# uController.net
KiCad netlist of a schematic drawn in Altium Designer
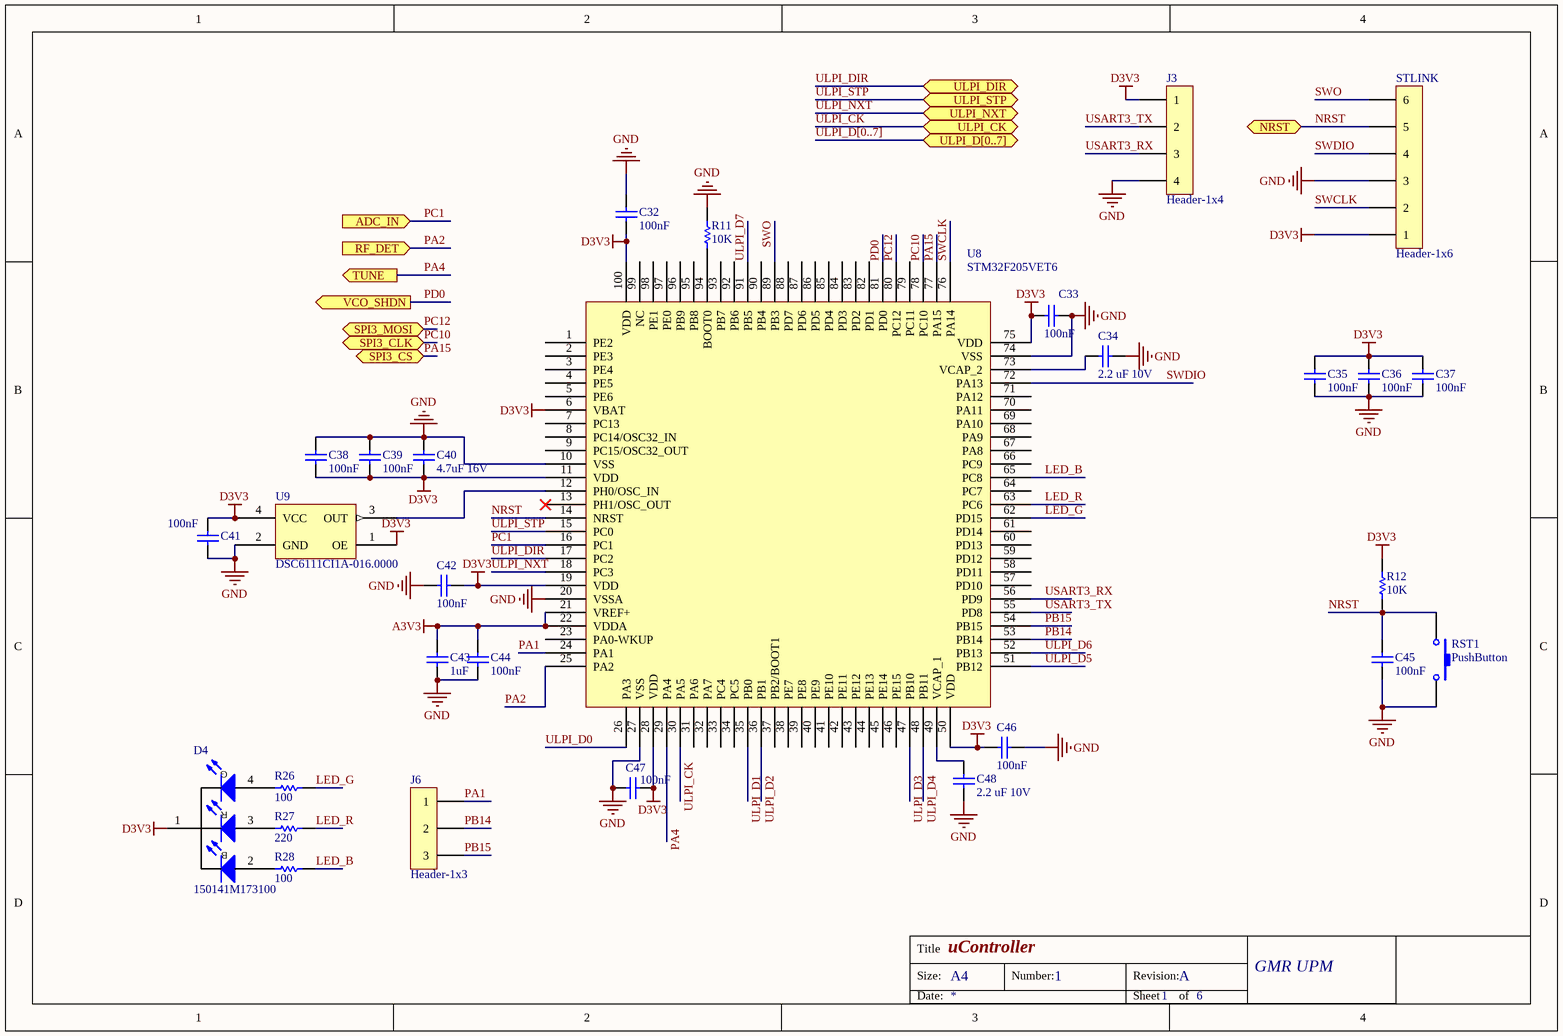
[diagram p0: uController.SchDoc]

(export (version "E")
  (design (tool "Eeschema 10.0.6"))
  (components
    (comp (ref "C32")
      (value "100nF")
      (footprint "0603 Cap")
      (description "CAP CER 0.1UF 16V X7R 0603")
      (fields
        (field (name "MANUFACTURER") "KEMET")
        (field (name "MANUFACTURER PART NUMBER") "C0603C104K4RACTU")
      )
      (libsource (lib "Componentes_base") (part "C0603C104K4RACTU"))
    )
    (comp (ref "C33")
      (value "100nF")
      (footprint "0603 Cap")
      (description "CAP CER 0.1UF 16V X7R 0603")
      (fields
        (field (name "MANUFACTURER") "KEMET")
        (field (name "MANUFACTURER PART NUMBER") "C0603C104K4RACTU")
      )
      (libsource (lib "Componentes_base") (part "C0603C104K4RACTU"))
    )
    (comp (ref "C34")
      (value "2.2 uF 10V")
      (footprint "0603 Cap")
      (description "CAP CER 2.2UF 10V X7R 0603")
      (fields
        (field (name "MANUFACTURER") "Samsung Electro-Mechanics America, Inc.")
        (field (name "MANUFACTURER PART NUMBER") "CL10B225KP8NNNC")
      )
      (libsource (lib "Componentes_base") (part "CL10B225KP8NNNC"))
    )
    (comp (ref "C35")
      (value "100nF")
      (footprint "0603 Cap")
      (description "CAP CER 0.1UF 16V X7R 0603")
      (fields
        (field (name "MANUFACTURER") "KEMET")
        (field (name "MANUFACTURER PART NUMBER") "C0603C104K4RACTU")
      )
      (libsource (lib "Componentes_base") (part "C0603C104K4RACTU"))
    )
    (comp (ref "C36")
      (value "100nF")
      (footprint "0603 Cap")
      (description "CAP CER 0.1UF 16V X7R 0603")
      (fields
        (field (name "MANUFACTURER") "KEMET")
        (field (name "MANUFACTURER PART NUMBER") "C0603C104K4RACTU")
      )
      (libsource (lib "Componentes_base") (part "C0603C104K4RACTU"))
    )
    (comp (ref "C37")
      (value "100nF")
      (footprint "0603 Cap")
      (description "CAP CER 0.1UF 16V X7R 0603")
      (fields
        (field (name "MANUFACTURER") "KEMET")
        (field (name "MANUFACTURER PART NUMBER") "C0603C104K4RACTU")
      )
      (libsource (lib "Componentes_base") (part "C0603C104K4RACTU"))
    )
    (comp (ref "C38")
      (value "100nF")
      (footprint "0603 Cap")
      (description "CAP CER 0.1UF 16V X7R 0603")
      (fields
        (field (name "MANUFACTURER") "KEMET")
        (field (name "MANUFACTURER PART NUMBER") "C0603C104K4RACTU")
      )
      (libsource (lib "Componentes_base") (part "C0603C104K4RACTU"))
    )
    (comp (ref "C39")
      (value "100nF")
      (footprint "0603 Cap")
      (description "CAP CER 0.1UF 16V X7R 0603")
      (fields
        (field (name "MANUFACTURER") "KEMET")
        (field (name "MANUFACTURER PART NUMBER") "C0603C104K4RACTU")
      )
      (libsource (lib "Componentes_base") (part "C0603C104K4RACTU"))
    )
    (comp (ref "C40")
      (value "4.7uF 16V")
      (footprint "0805 CAP")
      (description "CAP CER 4.7UF 16V X7R 0805")
      (fields
        (field (name "MANUFACTURER") "Murata Electronics North America")
        (field (name "MANUFACTURER PART NUMBER") "GRM21BR71C475KE51L")
      )
      (libsource (lib "Componentes_base") (part "GRM21BR71C475KE51L"))
    )
    (comp (ref "C41")
      (value "100nF")
      (footprint "0603 Cap")
      (description "CAP CER 0.1UF 16V X7R 0603")
      (fields
        (field (name "MANUFACTURER") "KEMET")
        (field (name "MANUFACTURER PART NUMBER") "C0603C104K4RACTU")
      )
      (libsource (lib "Componentes_base") (part "C0603C104K4RACTU"))
    )
    (comp (ref "C42")
      (value "100nF")
      (footprint "0603 Cap")
      (description "CAP CER 0.1UF 16V X7R 0603")
      (fields
        (field (name "MANUFACTURER") "KEMET")
        (field (name "MANUFACTURER PART NUMBER") "C0603C104K4RACTU")
      )
      (libsource (lib "Componentes_base") (part "C0603C104K4RACTU"))
    )
    (comp (ref "C43")
      (value "1uF")
      (footprint "0603 Cap")
      (description "CAP CER 1UF 16V X7R 0603")
      (fields
        (field (name "MANUFACTURER") "Samsung Electro-Mechanics America, Inc.")
        (field (name "MANUFACTURER PART NUMBER") "CL10B105MO8NNWC")
      )
      (libsource (lib "Componentes_base") (part "CL10B105MO8NNWC"))
    )
    (comp (ref "C44")
      (value "100nF")
      (footprint "0603 Cap")
      (description "CAP CER 0.1UF 16V X7R 0603")
      (fields
        (field (name "MANUFACTURER") "KEMET")
        (field (name "MANUFACTURER PART NUMBER") "C0603C104K4RACTU")
      )
      (libsource (lib "Componentes_base") (part "C0603C104K4RACTU"))
    )
    (comp (ref "C45")
      (value "100nF")
      (footprint "0603 Cap")
      (description "CAP CER 0.1UF 16V X7R 0603")
      (fields
        (field (name "MANUFACTURER") "KEMET")
        (field (name "MANUFACTURER PART NUMBER") "C0603C104K4RACTU")
      )
      (libsource (lib "Componentes_base") (part "C0603C104K4RACTU"))
    )
    (comp (ref "C46")
      (value "100nF")
      (footprint "0603 Cap")
      (description "CAP CER 0.1UF 16V X7R 0603")
      (fields
        (field (name "MANUFACTURER") "KEMET")
        (field (name "MANUFACTURER PART NUMBER") "C0603C104K4RACTU")
      )
      (libsource (lib "Componentes_base") (part "C0603C104K4RACTU"))
    )
    (comp (ref "C47")
      (value "100nF")
      (footprint "0603 Cap")
      (description "CAP CER 0.1UF 16V X7R 0603")
      (fields
        (field (name "MANUFACTURER") "KEMET")
        (field (name "MANUFACTURER PART NUMBER") "C0603C104K4RACTU")
      )
      (libsource (lib "Componentes_base") (part "C0603C104K4RACTU"))
    )
    (comp (ref "C48")
      (value "2.2 uF 10V")
      (footprint "0603 Cap")
      (description "CAP CER 2.2UF 10V X7R 0603")
      (fields
        (field (name "MANUFACTURER") "Samsung Electro-Mechanics America, Inc.")
        (field (name "MANUFACTURER PART NUMBER") "CL10B225KP8NNNC")
      )
      (libsource (lib "Componentes_base") (part "CL10B225KP8NNNC"))
    )
    (comp (ref "D4")
      (value "150141M173100")
      (footprint "DFN270P320X210-4N")
      (description "LED RGB CLEAR 1411 SMD")
      (fields (field (name "MANUFACTURER") "Wurth Electronics Inc."))
      (libsource (lib "Componentes_base") (part "150141M173100"))
    )
    (comp (ref "J3")
      (value "Header-1x4")
      (footprint "HEADER-1X4")
      (libsource (lib "B105connectors") (part "Header-1x4"))
    )
    (comp (ref "J6")
      (value "Header-1x3")
      (footprint "Header-1x3-Jumper")
      (libsource (lib "B105lib") (part "Header-1x3"))
    )
    (comp (ref "R11")
      (value "10K")
      (footprint "0603 Res")
      (description "RES SMD 10K OHM 1% 1/10W 0603")
      (fields
        (field (name "MANUFACTURER") "Yageo")
        (field (name "MANUFACTURER PART NUMBER") "RC0603FR-0710KL")
      )
      (libsource (lib "Componentes_base") (part "RC0603FR-0710KL"))
    )
    (comp (ref "R12")
      (value "10K")
      (footprint "0603 Res")
      (description "RES SMD 10K OHM 1% 1/10W 0603")
      (fields
        (field (name "MANUFACTURER") "Yageo")
        (field (name "MANUFACTURER PART NUMBER") "RC0603FR-0710KL")
      )
      (libsource (lib "Componentes_base") (part "RC0603FR-0710KL"))
    )
    (comp (ref "R26")
      (value "100")
      (footprint "RESC1005X04L")
      (description "RES 100 OHM 1/16W 1% 0402 SMD")
      (fields
        (field (name "MANUFACTURER") "Rohm Semiconductor")
        (field (name "MANUFACTURER PART NUMBER") "MCR01MRTF1000")
      )
      (libsource (lib "Componentes_base") (part "MCR01MRTF1000"))
    )
    (comp (ref "R27")
      (value "220")
      (footprint "RESC1005X04L")
      (description "RES SMD 220 OHM 1% 1/16W 0402")
      (fields
        (field (name "MANUFACTURER") "Yageo")
        (field (name "MANUFACTURER PART NUMBER") "RC0402FR-07220RL")
      )
      (libsource (lib "Componentes_base") (part "RC0402FR-07220RL"))
    )
    (comp (ref "R28")
      (value "100")
      (footprint "RESC1005X04L")
      (description "RES 100 OHM 1/16W 1% 0402 SMD")
      (fields
        (field (name "MANUFACTURER") "Rohm Semiconductor")
        (field (name "MANUFACTURER PART NUMBER") "MCR01MRTF1000")
      )
      (libsource (lib "Componentes_base") (part "MCR01MRTF1000"))
    )
    (comp (ref "RST1")
      (value "PushButton")
      (footprint "PushButton")
      (libsource (lib "B105lib") (part "PushButton"))
    )
    (comp (ref "STLINK")
      (value "Header-1x6")
      (footprint "Header-1x6")
      (libsource (lib "B105connectors") (part "Header-1x6"))
    )
    (comp (ref "U8")
      (value "STM32F205VET6")
      (footprint "LQFP-100")
      (description "IC MCU 32BIT 512KB FLASH 100LQFP")
      (fields (field (name "MANUFACTURER") "STMicroelectronics"))
      (libsource (lib "Componentes_base") (part "STM32F205VET6"))
    )
    (comp (ref "U9")
      (value "DSC6111CI1A-016.0000")
      (footprint "DFN 3.2x2.5")
      (description "ULTRA-LOW POWER,MEMS OSCILLATOR,")
      (fields (field (name "MANUFACTURER") "Microchip Technology"))
      (libsource (lib "Componentes_base") (part "DSC6111CI1A-016.0000"))
    )
  )
  (nets
    (net (code "1") (name "/LED_B") (class "Default")
      (node (ref "R28") (pin "2") (pinfunction "2_2") (pintype "passive"))
      (node (ref "U8") (pin "65") (pinfunction "PC8_65") (pintype "passive"))
    )
    (net (code "2") (name "/LED_G") (class "Default")
      (node (ref "R26") (pin "2") (pinfunction "2_2") (pintype "passive"))
      (node (ref "U8") (pin "62") (pinfunction "PD15_62") (pintype "passive"))
    )
    (net (code "3") (name "/LED_R") (class "Default")
      (node (ref "R27") (pin "2") (pinfunction "2_2") (pintype "passive"))
      (node (ref "U8") (pin "63") (pinfunction "PC6_63") (pintype "passive"))
    )
    (net (code "4") (name "/NRST") (class "Default")
      (node (ref "C45") (pin "2") (pinfunction "2_2") (pintype "passive"))
      (node (ref "R12") (pin "1") (pinfunction "1_1") (pintype "passive"))
      (node (ref "RST1") (pin "1") (pinfunction "1_1") (pintype "passive"))
      (node (ref "STLINK") (pin "5") (pinfunction "5_5") (pintype "passive"))
      (node (ref "U8") (pin "14") (pinfunction "NRST_14") (pintype "passive"))
    )
    (net (code "5") (name "/PA1") (class "Default")
      (node (ref "J6") (pin "1") (pinfunction "1_1") (pintype "passive"))
      (node (ref "U8") (pin "24") (pinfunction "PA1_24") (pintype "passive"))
    )
    (net (code "6") (name "/PA2") (class "Default")
      (node (ref "U8") (pin "25") (pinfunction "PA2_25") (pintype "passive"))
    )
    (net (code "7") (name "/PA4") (class "Default")
      (node (ref "U8") (pin "29") (pinfunction "PA4_29") (pintype "passive"))
    )
    (net (code "8") (name "/PA15") (class "Default")
      (node (ref "U8") (pin "77") (pinfunction "PA15_77") (pintype "passive"))
    )
    (net (code "9") (name "/PB14") (class "Default")
      (node (ref "J6") (pin "2") (pinfunction "2_2") (pintype "passive"))
      (node (ref "U8") (pin "53") (pinfunction "PB14_53") (pintype "passive"))
    )
    (net (code "10") (name "/PB15") (class "Default")
      (node (ref "J6") (pin "3") (pinfunction "3_3") (pintype "passive"))
      (node (ref "U8") (pin "54") (pinfunction "PB15_54") (pintype "passive"))
    )
    (net (code "11") (name "/PC1") (class "Default")
      (node (ref "U8") (pin "16") (pinfunction "PC1_16") (pintype "passive"))
    )
    (net (code "12") (name "/PC10") (class "Default")
      (node (ref "U8") (pin "78") (pinfunction "PC10_78") (pintype "passive"))
    )
    (net (code "13") (name "/PC12") (class "Default")
      (node (ref "U8") (pin "80") (pinfunction "PC12_80") (pintype "passive"))
    )
    (net (code "14") (name "/PD0") (class "Default")
      (node (ref "U8") (pin "81") (pinfunction "PD0_81") (pintype "passive"))
    )
    (net (code "15") (name "/SWCLK") (class "Default")
      (node (ref "STLINK") (pin "2") (pinfunction "2_2") (pintype "passive"))
      (node (ref "U8") (pin "76") (pinfunction "PA14_76") (pintype "passive"))
    )
    (net (code "16") (name "/SWDIO") (class "Default")
      (node (ref "STLINK") (pin "4") (pinfunction "4_4") (pintype "passive"))
      (node (ref "U8") (pin "72") (pinfunction "PA13_72") (pintype "passive"))
    )
    (net (code "17") (name "/SWO") (class "Default")
      (node (ref "STLINK") (pin "6") (pinfunction "6_6") (pintype "passive"))
      (node (ref "U8") (pin "89") (pinfunction "PB3_89") (pintype "passive"))
    )
    (net (code "18") (name "/ULPI_CK") (class "Default")
      (node (ref "U8") (pin "30") (pinfunction "PA5_30") (pintype "passive"))
    )
    (net (code "19") (name "/ULPI_D0") (class "Default")
      (node (ref "U8") (pin "26") (pinfunction "PA3_26") (pintype "passive"))
    )
    (net (code "20") (name "/ULPI_D1") (class "Default")
      (node (ref "U8") (pin "35") (pinfunction "PB0_35") (pintype "passive"))
    )
    (net (code "21") (name "/ULPI_D2") (class "Default")
      (node (ref "U8") (pin "36") (pinfunction "PB1_36") (pintype "passive"))
    )
    (net (code "22") (name "/ULPI_D3") (class "Default")
      (node (ref "U8") (pin "47") (pinfunction "PB10_47") (pintype "passive"))
    )
    (net (code "23") (name "/ULPI_D4") (class "Default")
      (node (ref "U8") (pin "48") (pinfunction "PB11_48") (pintype "passive"))
    )
    (net (code "24") (name "/ULPI_D5") (class "Default")
      (node (ref "U8") (pin "51") (pinfunction "PB12_51") (pintype "passive"))
    )
    (net (code "25") (name "/ULPI_D6") (class "Default")
      (node (ref "U8") (pin "52") (pinfunction "PB13_52") (pintype "passive"))
    )
    (net (code "26") (name "/ULPI_D7") (class "Default")
      (node (ref "U8") (pin "91") (pinfunction "PB5_91") (pintype "passive"))
    )
    (net (code "27") (name "/ULPI_DIR") (class "Default")
      (node (ref "U8") (pin "17") (pinfunction "PC2_17") (pintype "passive"))
    )
    (net (code "29") (name "/ULPI_NXT") (class "Default")
      (node (ref "U8") (pin "18") (pinfunction "PC3_18") (pintype "passive"))
    )
    (net (code "30") (name "/ULPI_STP") (class "Default")
      (node (ref "U8") (pin "15") (pinfunction "PC0_15") (pintype "passive"))
    )
    (net (code "31") (name "/USART3_RX") (class "Default")
      (node (ref "J3") (pin "3") (pinfunction "3_3") (pintype "passive"))
      (node (ref "U8") (pin "56") (pinfunction "PD9_56") (pintype "passive"))
    )
    (net (code "32") (name "/USART3_TX") (class "Default")
      (node (ref "J3") (pin "2") (pinfunction "2_2") (pintype "passive"))
      (node (ref "U8") (pin "55") (pinfunction "PD8_55") (pintype "passive"))
    )
    (net (code "33") (name "A3V3") (class "Default")
      (node (ref "C43") (pin "2") (pinfunction "2_2") (pintype "passive"))
      (node (ref "C44") (pin "1") (pinfunction "1_1") (pintype "passive"))
      (node (ref "U8") (pin "21") (pinfunction "VREF+_21") (pintype "passive"))
      (node (ref "U8") (pin "22") (pinfunction "VDDA_22") (pintype "passive"))
    )
    (net (code "34") (name "D3V3") (class "Default")
      (node (ref "C32") (pin "2") (pinfunction "2_2") (pintype "passive"))
      (node (ref "C33") (pin "1") (pinfunction "1_1") (pintype "passive"))
      (node (ref "C35") (pin "2") (pinfunction "2_2") (pintype "passive"))
      (node (ref "C36") (pin "2") (pinfunction "2_2") (pintype "passive"))
      (node (ref "C37") (pin "2") (pinfunction "2_2") (pintype "passive"))
      (node (ref "C38") (pin "1") (pinfunction "1_1") (pintype "passive"))
      (node (ref "C39") (pin "1") (pinfunction "1_1") (pintype "passive"))
      (node (ref "C40") (pin "1") (pinfunction "1_1") (pintype "passive"))
      (node (ref "C41") (pin "2") (pinfunction "2_2") (pintype "passive"))
      (node (ref "C42") (pin "1") (pinfunction "1_1") (pintype "passive"))
      (node (ref "C46") (pin "2") (pinfunction "2_2") (pintype "passive"))
      (node (ref "C47") (pin "1") (pinfunction "1_1") (pintype "passive"))
      (node (ref "D4") (pin "1") (pinfunction "A_1") (pintype "passive"))
      (node (ref "J3") (pin "1") (pinfunction "1_1") (pintype "passive"))
      (node (ref "R12") (pin "2") (pinfunction "2_2") (pintype "passive"))
      (node (ref "STLINK") (pin "1") (pinfunction "1_1") (pintype "passive"))
      (node (ref "U8") (pin "100") (pinfunction "VDD_100") (pintype "passive"))
      (node (ref "U8") (pin "11") (pinfunction "VDD_11") (pintype "passive"))
      (node (ref "U8") (pin "19") (pinfunction "VDD_19") (pintype "passive"))
      (node (ref "U8") (pin "28") (pinfunction "VDD_28") (pintype "passive"))
      (node (ref "U8") (pin "50") (pinfunction "VDD_50") (pintype "passive"))
      (node (ref "U8") (pin "6") (pinfunction "VBAT_6") (pintype "passive"))
      (node (ref "U8") (pin "75") (pinfunction "VDD_75") (pintype "passive"))
      (node (ref "U9") (pin "1") (pinfunction "OE_1") (pintype "passive"))
      (node (ref "U9") (pin "4") (pinfunction "VCC_4") (pintype "power_in"))
    )
    (net (code "35") (name "GND") (class "Default")
      (node (ref "C32") (pin "1") (pinfunction "1_1") (pintype "passive"))
      (node (ref "C33") (pin "2") (pinfunction "2_2") (pintype "passive"))
      (node (ref "C34") (pin "1") (pinfunction "1_1") (pintype "passive"))
      (node (ref "C35") (pin "1") (pinfunction "1_1") (pintype "passive"))
      (node (ref "C36") (pin "1") (pinfunction "1_1") (pintype "passive"))
      (node (ref "C37") (pin "1") (pinfunction "1_1") (pintype "passive"))
      (node (ref "C38") (pin "2") (pinfunction "2_2") (pintype "passive"))
      (node (ref "C39") (pin "2") (pinfunction "2_2") (pintype "passive"))
      (node (ref "C40") (pin "2") (pinfunction "2_2") (pintype "passive"))
      (node (ref "C41") (pin "1") (pinfunction "1_1") (pintype "passive"))
      (node (ref "C42") (pin "2") (pinfunction "2_2") (pintype "passive"))
      (node (ref "C43") (pin "1") (pinfunction "1_1") (pintype "passive"))
      (node (ref "C44") (pin "2") (pinfunction "2_2") (pintype "passive"))
      (node (ref "C45") (pin "1") (pinfunction "1_1") (pintype "passive"))
      (node (ref "C46") (pin "1") (pinfunction "1_1") (pintype "passive"))
      (node (ref "C47") (pin "2") (pinfunction "2_2") (pintype "passive"))
      (node (ref "C48") (pin "1") (pinfunction "1_1") (pintype "passive"))
      (node (ref "J3") (pin "4") (pinfunction "4_4") (pintype "passive"))
      (node (ref "R11") (pin "2") (pinfunction "2_2") (pintype "passive"))
      (node (ref "RST1") (pin "2") (pinfunction "2_2") (pintype "passive"))
      (node (ref "STLINK") (pin "3") (pinfunction "3_3") (pintype "passive"))
      (node (ref "U8") (pin "10") (pinfunction "VSS_10") (pintype "passive"))
      (node (ref "U8") (pin "20") (pinfunction "VSSA_20") (pintype "passive"))
      (node (ref "U8") (pin "27") (pinfunction "VSS_27") (pintype "passive"))
      (node (ref "U8") (pin "74") (pinfunction "VSS_74") (pintype "passive"))
      (node (ref "U9") (pin "2") (pinfunction "GND_2") (pintype "power_in"))
    )
    (net (code "36") (name "Net-(D4-C-Pad2)") (class "Default")
      (node (ref "D4") (pin "2") (pinfunction "C_2") (pintype "passive"))
      (node (ref "R28") (pin "1") (pinfunction "1_1") (pintype "passive"))
    )
    (net (code "37") (name "Net-(D4-C-Pad3)") (class "Default")
      (node (ref "D4") (pin "3") (pinfunction "C_3") (pintype "passive"))
      (node (ref "R27") (pin "1") (pinfunction "1_1") (pintype "passive"))
    )
    (net (code "38") (name "Net-(D4-C-Pad4)") (class "Default")
      (node (ref "D4") (pin "4") (pinfunction "C_4") (pintype "passive"))
      (node (ref "R26") (pin "1") (pinfunction "1_1") (pintype "passive"))
    )
    (net (code "39") (name "Net-(U8-BOOT0)") (class "Default")
      (node (ref "R11") (pin "1") (pinfunction "1_1") (pintype "passive"))
      (node (ref "U8") (pin "94") (pinfunction "BOOT0_94") (pintype "passive"))
    )
    (net (code "40") (name "Net-(U8-PH0{slash}OSC_IN)") (class "Default")
      (node (ref "U8") (pin "12") (pinfunction "PH0/OSC_IN_12") (pintype "passive"))
      (node (ref "U9") (pin "3") (pinfunction "OUT_3") (pintype "output"))
    )
    (net (code "41") (name "Net-(U8-VCAP_1)") (class "Default")
      (node (ref "C48") (pin "2") (pinfunction "2_2") (pintype "passive"))
      (node (ref "U8") (pin "49") (pinfunction "VCAP_1_49") (pintype "passive"))
    )
    (net (code "42") (name "Net-(U8-VCAP_2)") (class "Default")
      (node (ref "C34") (pin "2") (pinfunction "2_2") (pintype "passive"))
      (node (ref "U8") (pin "73") (pinfunction "VCAP_2_73") (pintype "passive"))
    )
    (net (code "43") (name "unconnected-(U8-NC-Pad99)") (class "Default")
      (node (ref "U8") (pin "99") (pinfunction "NC_99") (pintype "passive"))
    )
    (net (code "44") (name "unconnected-(U8-PA0-WKUP-Pad23)") (class "Default")
      (node (ref "U8") (pin "23") (pinfunction "PA0-WKUP_23") (pintype "passive"))
    )
    (net (code "45") (name "unconnected-(U8-PA6-Pad31)") (class "Default")
      (node (ref "U8") (pin "31") (pinfunction "PA6_31") (pintype "passive"))
    )
    (net (code "46") (name "unconnected-(U8-PA7-Pad32)") (class "Default")
      (node (ref "U8") (pin "32") (pinfunction "PA7_32") (pintype "passive"))
    )
    (net (code "47") (name "unconnected-(U8-PA8-Pad67)") (class "Default")
      (node (ref "U8") (pin "67") (pinfunction "PA8_67") (pintype "passive"))
    )
    (net (code "48") (name "unconnected-(U8-PA9-Pad68)") (class "Default")
      (node (ref "U8") (pin "68") (pinfunction "PA9_68") (pintype "passive"))
    )
    (net (code "49") (name "unconnected-(U8-PA10-Pad69)") (class "Default")
      (node (ref "U8") (pin "69") (pinfunction "PA10_69") (pintype "passive"))
    )
    (net (code "50") (name "unconnected-(U8-PA11-Pad70)") (class "Default")
      (node (ref "U8") (pin "70") (pinfunction "PA11_70") (pintype "passive"))
    )
    (net (code "51") (name "unconnected-(U8-PA12-Pad71)") (class "Default")
      (node (ref "U8") (pin "71") (pinfunction "PA12_71") (pintype "passive"))
    )
    (net (code "52") (name "unconnected-(U8-PB2{slash}BOOT1-Pad37)") (class "Default")
      (node (ref "U8") (pin "37") (pinfunction "PB2/BOOT1_37") (pintype "passive"))
    )
    (net (code "53") (name "unconnected-(U8-PB4-Pad90)") (class "Default")
      (node (ref "U8") (pin "90") (pinfunction "PB4_90") (pintype "passive"))
    )
    (net (code "54") (name "unconnected-(U8-PB6-Pad92)") (class "Default")
      (node (ref "U8") (pin "92") (pinfunction "PB6_92") (pintype "passive"))
    )
    (net (code "55") (name "unconnected-(U8-PB7-Pad93)") (class "Default")
      (node (ref "U8") (pin "93") (pinfunction "PB7_93") (pintype "passive"))
    )
    (net (code "56") (name "unconnected-(U8-PB8-Pad95)") (class "Default")
      (node (ref "U8") (pin "95") (pinfunction "PB8_95") (pintype "passive"))
    )
    (net (code "57") (name "unconnected-(U8-PB9-Pad96)") (class "Default")
      (node (ref "U8") (pin "96") (pinfunction "PB9_96") (pintype "passive"))
    )
    (net (code "58") (name "unconnected-(U8-PC4-Pad33)") (class "Default")
      (node (ref "U8") (pin "33") (pinfunction "PC4_33") (pintype "passive"))
    )
    (net (code "59") (name "unconnected-(U8-PC5-Pad34)") (class "Default")
      (node (ref "U8") (pin "34") (pinfunction "PC5_34") (pintype "passive"))
    )
    (net (code "60") (name "unconnected-(U8-PC7-Pad64)") (class "Default")
      (node (ref "U8") (pin "64") (pinfunction "PC7_64") (pintype "passive"))
    )
    (net (code "61") (name "unconnected-(U8-PC9-Pad66)") (class "Default")
      (node (ref "U8") (pin "66") (pinfunction "PC9_66") (pintype "passive"))
    )
    (net (code "62") (name "unconnected-(U8-PC11-Pad79)") (class "Default")
      (node (ref "U8") (pin "79") (pinfunction "PC11_79") (pintype "passive"))
    )
    (net (code "63") (name "unconnected-(U8-PC13-Pad7)") (class "Default")
      (node (ref "U8") (pin "7") (pinfunction "PC13_7") (pintype "passive"))
    )
    (net (code "64") (name "unconnected-(U8-PC14{slash}OSC32_IN-Pad8)") (class "Default")
      (node (ref "U8") (pin "8") (pinfunction "PC14/OSC32_IN_8") (pintype "passive"))
    )
    (net (code "65") (name "unconnected-(U8-PC15{slash}OSC32_OUT-Pad9)") (class "Default")
      (node (ref "U8") (pin "9") (pinfunction "PC15/OSC32_OUT_9") (pintype "passive"))
    )
    (net (code "66") (name "unconnected-(U8-PD1-Pad82)") (class "Default")
      (node (ref "U8") (pin "82") (pinfunction "PD1_82") (pintype "passive"))
    )
    (net (code "67") (name "unconnected-(U8-PD2-Pad83)") (class "Default")
      (node (ref "U8") (pin "83") (pinfunction "PD2_83") (pintype "passive"))
    )
    (net (code "68") (name "unconnected-(U8-PD3-Pad84)") (class "Default")
      (node (ref "U8") (pin "84") (pinfunction "PD3_84") (pintype "passive"))
    )
    (net (code "69") (name "unconnected-(U8-PD4-Pad85)") (class "Default")
      (node (ref "U8") (pin "85") (pinfunction "PD4_85") (pintype "passive"))
    )
    (net (code "70") (name "unconnected-(U8-PD5-Pad86)") (class "Default")
      (node (ref "U8") (pin "86") (pinfunction "PD5_86") (pintype "passive"))
    )
    (net (code "71") (name "unconnected-(U8-PD6-Pad87)") (class "Default")
      (node (ref "U8") (pin "87") (pinfunction "PD6_87") (pintype "passive"))
    )
    (net (code "72") (name "unconnected-(U8-PD7-Pad88)") (class "Default")
      (node (ref "U8") (pin "88") (pinfunction "PD7_88") (pintype "passive"))
    )
    (net (code "73") (name "unconnected-(U8-PD10-Pad57)") (class "Default")
      (node (ref "U8") (pin "57") (pinfunction "PD10_57") (pintype "passive"))
    )
    (net (code "74") (name "unconnected-(U8-PD11-Pad58)") (class "Default")
      (node (ref "U8") (pin "58") (pinfunction "PD11_58") (pintype "passive"))
    )
    (net (code "75") (name "unconnected-(U8-PD12-Pad59)") (class "Default")
      (node (ref "U8") (pin "59") (pinfunction "PD12_59") (pintype "passive"))
    )
    (net (code "76") (name "unconnected-(U8-PD13-Pad60)") (class "Default")
      (node (ref "U8") (pin "60") (pinfunction "PD13_60") (pintype "passive"))
    )
    (net (code "77") (name "unconnected-(U8-PD14-Pad61)") (class "Default")
      (node (ref "U8") (pin "61") (pinfunction "PD14_61") (pintype "passive"))
    )
    (net (code "78") (name "unconnected-(U8-PE0-Pad97)") (class "Default")
      (node (ref "U8") (pin "97") (pinfunction "PE0_97") (pintype "passive"))
    )
    (net (code "79") (name "unconnected-(U8-PE1-Pad98)") (class "Default")
      (node (ref "U8") (pin "98") (pinfunction "PE1_98") (pintype "passive"))
    )
    (net (code "80") (name "unconnected-(U8-PE2-Pad1)") (class "Default")
      (node (ref "U8") (pin "1") (pinfunction "PE2_1") (pintype "passive"))
    )
    (net (code "81") (name "unconnected-(U8-PE3-Pad2)") (class "Default")
      (node (ref "U8") (pin "2") (pinfunction "PE3_2") (pintype "passive"))
    )
    (net (code "82") (name "unconnected-(U8-PE4-Pad3)") (class "Default")
      (node (ref "U8") (pin "3") (pinfunction "PE4_3") (pintype "passive"))
    )
    (net (code "83") (name "unconnected-(U8-PE5-Pad4)") (class "Default")
      (node (ref "U8") (pin "4") (pinfunction "PE5_4") (pintype "passive"))
    )
    (net (code "84") (name "unconnected-(U8-PE6-Pad5)") (class "Default")
      (node (ref "U8") (pin "5") (pinfunction "PE6_5") (pintype "passive"))
    )
    (net (code "85") (name "unconnected-(U8-PE7-Pad38)") (class "Default")
      (node (ref "U8") (pin "38") (pinfunction "PE7_38") (pintype "passive"))
    )
    (net (code "86") (name "unconnected-(U8-PE8-Pad39)") (class "Default")
      (node (ref "U8") (pin "39") (pinfunction "PE8_39") (pintype "passive"))
    )
    (net (code "87") (name "unconnected-(U8-PE9-Pad40)") (class "Default")
      (node (ref "U8") (pin "40") (pinfunction "PE9_40") (pintype "passive"))
    )
    (net (code "88") (name "unconnected-(U8-PE10-Pad41)") (class "Default")
      (node (ref "U8") (pin "41") (pinfunction "PE10_41") (pintype "passive"))
    )
    (net (code "89") (name "unconnected-(U8-PE11-Pad42)") (class "Default")
      (node (ref "U8") (pin "42") (pinfunction "PE11_42") (pintype "passive"))
    )
    (net (code "90") (name "unconnected-(U8-PE12-Pad43)") (class "Default")
      (node (ref "U8") (pin "43") (pinfunction "PE12_43") (pintype "passive"))
    )
    (net (code "91") (name "unconnected-(U8-PE13-Pad44)") (class "Default")
      (node (ref "U8") (pin "44") (pinfunction "PE13_44") (pintype "passive"))
    )
    (net (code "92") (name "unconnected-(U8-PE14-Pad45)") (class "Default")
      (node (ref "U8") (pin "45") (pinfunction "PE14_45") (pintype "passive"))
    )
    (net (code "93") (name "unconnected-(U8-PE15-Pad46)") (class "Default")
      (node (ref "U8") (pin "46") (pinfunction "PE15_46") (pintype "passive"))
    )
    (net (code "94") (name "unconnected-(U8-PH1{slash}OSC_OUT-Pad13)") (class "Default")
      (node (ref "U8") (pin "13") (pinfunction "PH1/OSC_OUT_13") (pintype "passive+no_connect"))
    )
  )
)
